# 1_power.net
KiCad netlist of a schematic drawn in Altium Designer
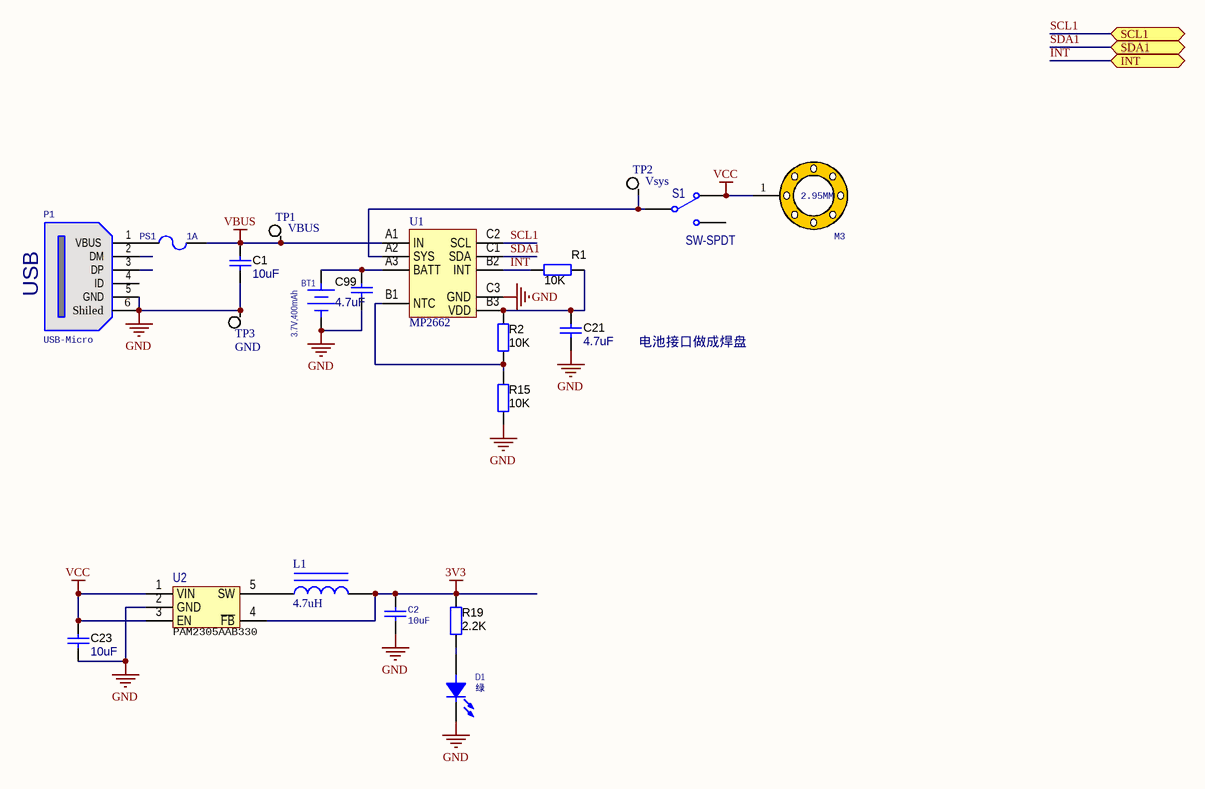
[diagram p0: 1.power.SchDoc]

(export (version "E")
  (design (tool "Eeschema 10.0.6"))
  (components
    (comp (ref "BT1")
      (value "3.7V,400mAh")
      (footprint "焊盘")
      (description "4.2V Li-lon")
      (fields (field (name "MANUFACTURER") "?"))
      (libsource (lib "03.常用器件") (part "Battery"))
    )
    (comp (ref "C1")
      (value "10uF")
      (footprint "0603")
      (description "CAP, CERM, 0.01uF, 100V, +/-5%, X7R, 0603")
      (fields (field (name "PARTNUMBER") "06031C103JAT2A") (field (name "MANUFACTURER") "AVX"))
      (libsource (lib "03.常用器件") (part "CAP1_npol"))
    )
    (comp (ref "C2")
      (value "10uF")
      (footprint "0603")
      (description "电容")
      (fields (field (name "PUBLISHER") "Altium Limited"))
      (libsource (lib "*") (part "Cap NP"))
    )
    (comp (ref "C21")
      (value "4.7uF")
      (footprint "0603")
      (description "CAP, CERM, 0.01uF, 100V, +/-5%, X7R, 0603")
      (fields (field (name "PARTNUMBER") "06031C103JAT2A") (field (name "MANUFACTURER") "AVX"))
      (libsource (lib "03.常用器件") (part "CAP1_npol"))
    )
    (comp (ref "C23")
      (value "10uF")
      (footprint "0603")
      (description "CAP, CERM, 0.01uF, 100V, +/-5%, X7R, 0603")
      (fields (field (name "PARTNUMBER") "06031C103JAT2A") (field (name "MANUFACTURER") "AVX"))
      (libsource (lib "03.常用器件") (part "CAP1_npol"))
    )
    (comp (ref "C99")
      (value "4.7uF")
      (footprint "0603")
      (description "CAP, CERM, 0.01uF, 100V, +/-5%, X7R, 0603")
      (fields (field (name "PARTNUMBER") "06031C103JAT2A") (field (name "MANUFACTURER") "AVX"))
      (libsource (lib "03.常用器件") (part "CAP1_npol"))
    )
    (comp (ref "D1")
      (value "绿")
      (footprint "0603LED")
      (fields (field (name "MANUFACTURER") "?"))
      (libsource (lib "03.常用器件") (part "LED1"))
    )
    (comp (ref "L1")
      (value "4.7uH")
      (footprint "4.7UH 0420 2.2A  4*4*2MM")
      (description "Magnetic-Core Inductor")
      (fields (field (name "PUBLISHER") "Altium Limited"))
      (libsource (lib "Miscellaneous Devices") (part "Inductor Iron"))
    )
    (comp (ref "M3") (value "2.95MM") (footprint "螺丝孔") (libsource (lib "labplus-connector") (part "screw")))
    (comp (ref "P1")
      (value "USB-Micro")
      (footprint "MICRO_USB2")
      (description "USB Connector")
      (libsource (lib "misc") (part "USB-Micro"))
    )
    (comp (ref "PS1")
      (value "1A")
      (footprint "1206")
      (description "保险管")
      (fields (field (name "MANUFACTURER") "?"))
      (libsource (lib "03.常用器件") (part "PS1"))
    )
    (comp (ref "R1")
      (value "10K")
      (footprint "0402")
      (description "RES, 1.0k ohm, 5%, 0.1W, 0603")
      (fields
        (field (name "PARTNUMBER") "RC0603JR-071KL")
        (field (name "MANUFACTURER") "Yageo America")
        (field (name "PUBLISHER") "Texas Instruments")
      )
      (libsource (lib "") (part "RES1_1"))
    )
    (comp (ref "R2")
      (value "10K")
      (footprint "0402")
      (description "RES, 1.0k ohm, 5%, 0.1W, 0603")
      (fields
        (field (name "PARTNUMBER") "RC0603JR-071KL")
        (field (name "MANUFACTURER") "Yageo America")
        (field (name "PUBLISHER") "Texas Instruments")
      )
      (libsource (lib "03.常用器件") (part "RES1"))
    )
    (comp (ref "R15")
      (value "10K")
      (footprint "0402")
      (description "RES, 1.0k ohm, 5%, 0.1W, 0603")
      (fields
        (field (name "PARTNUMBER") "RC0603JR-071KL")
        (field (name "MANUFACTURER") "Yageo America")
        (field (name "PUBLISHER") "Texas Instruments")
      )
      (libsource (lib "03.常用器件") (part "RES1"))
    )
    (comp (ref "R19")
      (value "2.2K")
      (footprint "0402")
      (description "RES, 1.0k ohm, 5%, 0.1W, 0603")
      (fields
        (field (name "PARTNUMBER") "RC0603JR-071KL")
        (field (name "MANUFACTURER") "Yageo America")
        (field (name "PUBLISHER") "Texas Instruments")
      )
      (libsource (lib "03.常用器件") (part "RES1"))
    )
    (comp (ref "S1")
      (value "SW-SPDT")
      (footprint "SW2")
      (description "SPDT Subminiature Toggle Switch, Right Angle Mounting, Vertical Actuation")
      (fields (field (name "PUBLISHER") "Altium Limited"))
      (libsource (lib "Miscellaneous Devices") (part "SW-SPDT"))
    )
    (comp (ref "TP1")
      (value "VBUS")
      (footprint "测试点")
      (description "Test Point")
      (libsource (lib "my_Schlib") (part "TP"))
    )
    (comp (ref "TP2")
      (value "Vsys")
      (footprint "测试点")
      (description "Test Point")
      (libsource (lib "my_Schlib") (part "TP"))
    )
    (comp (ref "TP3")
      (value "GND")
      (footprint "测试点")
      (description "Test Point")
      (libsource (lib "my_Schlib") (part "TP"))
    )
    (comp (ref "U1") (value "MP2662") (footprint "WLCSP-9") (libsource (lib "Schlib1") (part "MP2662")))
    (comp (ref "U2")
      (value "PAM2305AAB330")
      (footprint "SOT23-5")
      (description "PAM2305AAB330 采用SOT-23 封装的2.5V 至5.5V 输入，1A 降压稳压  器")
      (libsource (lib "Schlib1") (part "PAM2305AAB330"))
    )
  )
  (nets
    (net (code "1") (name "/INT") (class "Default")
      (node (ref "R1") (pin "1") (pinfunction "1_1") (pintype "passive"))
      (node (ref "U1") (pin "B2") (pinfunction "INT_B2") (pintype "passive"))
    )
    (net (code "2") (name "/SCL1") (class "Default")
      (node (ref "U1") (pin "C2") (pinfunction "SCL_C2") (pintype "passive"))
    )
    (net (code "3") (name "/SDA1") (class "Default")
      (node (ref "U1") (pin "C1") (pinfunction "SDA_C1") (pintype "passive"))
    )
    (net (code "4") (name "3V3") (class "Default")
      (node (ref "C2") (pin "1") (pinfunction "1_1") (pintype "passive"))
      (node (ref "L1") (pin "2") (pinfunction "2_2") (pintype "passive"))
      (node (ref "R19") (pin "1") (pinfunction "1_1") (pintype "passive"))
      (node (ref "U2") (pin "4") (pinfunction "~{FB}_4") (pintype "power_in"))
    )
    (net (code "5") (name "GND") (class "Default")
      (node (ref "BT1") (pin "2") (pinfunction "-_2") (pintype "passive"))
      (node (ref "C1") (pin "2") (pinfunction "2_2") (pintype "passive"))
      (node (ref "C2") (pin "2") (pinfunction "2_2") (pintype "passive"))
      (node (ref "C21") (pin "2") (pinfunction "2_2") (pintype "passive"))
      (node (ref "C23") (pin "2") (pinfunction "2_2") (pintype "passive"))
      (node (ref "C99") (pin "2") (pinfunction "2_2") (pintype "passive"))
      (node (ref "D1") (pin "C") (pinfunction "CATHODE_C") (pintype "passive"))
      (node (ref "P1") (pin "5") (pinfunction "GND_5") (pintype "passive"))
      (node (ref "P1") (pin "6") (pinfunction "Shiled_6") (pintype "passive"))
      (node (ref "R15") (pin "2") (pinfunction "2_2") (pintype "passive"))
      (node (ref "TP3") (pin "1") (pinfunction "1_1") (pintype "passive"))
      (node (ref "U1") (pin "C3") (pinfunction "GND_C3") (pintype "passive"))
      (node (ref "U2") (pin "2") (pinfunction "GND_2") (pintype "passive"))
    )
    (net (code "6") (name "Net-(BT1-+)") (class "Default")
      (node (ref "BT1") (pin "1") (pinfunction "+_1") (pintype "passive"))
      (node (ref "C99") (pin "1") (pinfunction "1_1") (pintype "passive"))
      (node (ref "U1") (pin "A3") (pinfunction "BATT_A3") (pintype "passive"))
    )
    (net (code "7") (name "Net-(D1-ANODE)") (class "Default")
      (node (ref "D1") (pin "A") (pinfunction "ANODE_A") (pintype "passive"))
      (node (ref "R19") (pin "2") (pinfunction "2_2") (pintype "passive"))
    )
    (net (code "8") (name "Net-(P1-VBUS)") (class "Default")
      (node (ref "P1") (pin "1") (pinfunction "VBUS_1") (pintype "passive"))
      (node (ref "PS1") (pin "1") (pinfunction "0_1") (pintype "passive"))
    )
    (net (code "9") (name "Net-(U1-NTC)") (class "Default")
      (node (ref "R15") (pin "1") (pinfunction "1_1") (pintype "passive"))
      (node (ref "R2") (pin "2") (pinfunction "2_2") (pintype "passive"))
      (node (ref "U1") (pin "B1") (pinfunction "NTC_B1") (pintype "power_in"))
    )
    (net (code "10") (name "Net-(U1-SYS)") (class "Default")
      (node (ref "S1") (pin "2") (pinfunction "2_2") (pintype "passive"))
      (node (ref "TP2") (pin "1") (pinfunction "1_1") (pintype "passive"))
      (node (ref "U1") (pin "A2") (pinfunction "SYS_A2") (pintype "passive"))
    )
    (net (code "11") (name "Net-(U1-VDD)") (class "Default")
      (node (ref "C21") (pin "1") (pinfunction "1_1") (pintype "passive"))
      (node (ref "R1") (pin "2") (pinfunction "2_2") (pintype "passive"))
      (node (ref "R2") (pin "1") (pinfunction "1_1") (pintype "passive"))
      (node (ref "U1") (pin "B3") (pinfunction "VDD_B3") (pintype "passive"))
    )
    (net (code "12") (name "Net-(U2-SW)") (class "Default")
      (node (ref "L1") (pin "1") (pinfunction "1_1") (pintype "passive"))
      (node (ref "U2") (pin "5") (pinfunction "SW_5") (pintype "passive"))
    )
    (net (code "13") (name "VBUS") (class "Default")
      (node (ref "C1") (pin "1") (pinfunction "1_1") (pintype "passive"))
      (node (ref "PS1") (pin "2") (pinfunction "1_2") (pintype "passive"))
      (node (ref "TP1") (pin "1") (pinfunction "1_1") (pintype "passive"))
      (node (ref "U1") (pin "A1") (pinfunction "IN_A1") (pintype "passive"))
    )
    (net (code "14") (name "VCC") (class "Default")
      (node (ref "C23") (pin "1") (pinfunction "1_1") (pintype "passive"))
      (node (ref "M3") (pin "1") (pinfunction "1_1") (pintype "passive"))
      (node (ref "S1") (pin "3") (pinfunction "3_3") (pintype "passive"))
      (node (ref "U2") (pin "1") (pinfunction "VIN_1") (pintype "passive"))
      (node (ref "U2") (pin "3") (pinfunction "EN_3") (pintype "passive"))
    )
    (net (code "15") (name "unconnected-(P1-DM-Pad2)") (class "Default")
      (node (ref "P1") (pin "2") (pinfunction "DM_2") (pintype "passive"))
    )
    (net (code "16") (name "unconnected-(P1-DP-Pad3)") (class "Default")
      (node (ref "P1") (pin "3") (pinfunction "DP_3") (pintype "passive"))
    )
    (net (code "17") (name "unconnected-(P1-ID-Pad4)") (class "Default")
      (node (ref "P1") (pin "4") (pinfunction "ID_4") (pintype "passive"))
    )
    (net (code "18") (name "unconnected-(S1-Pad1)") (class "Default")
      (node (ref "S1") (pin "1") (pinfunction "1_1") (pintype "passive"))
    )
  )
)
